# Adafruit_CAP1188.net
KiCad netlist of a schematic drawn in EAGLE
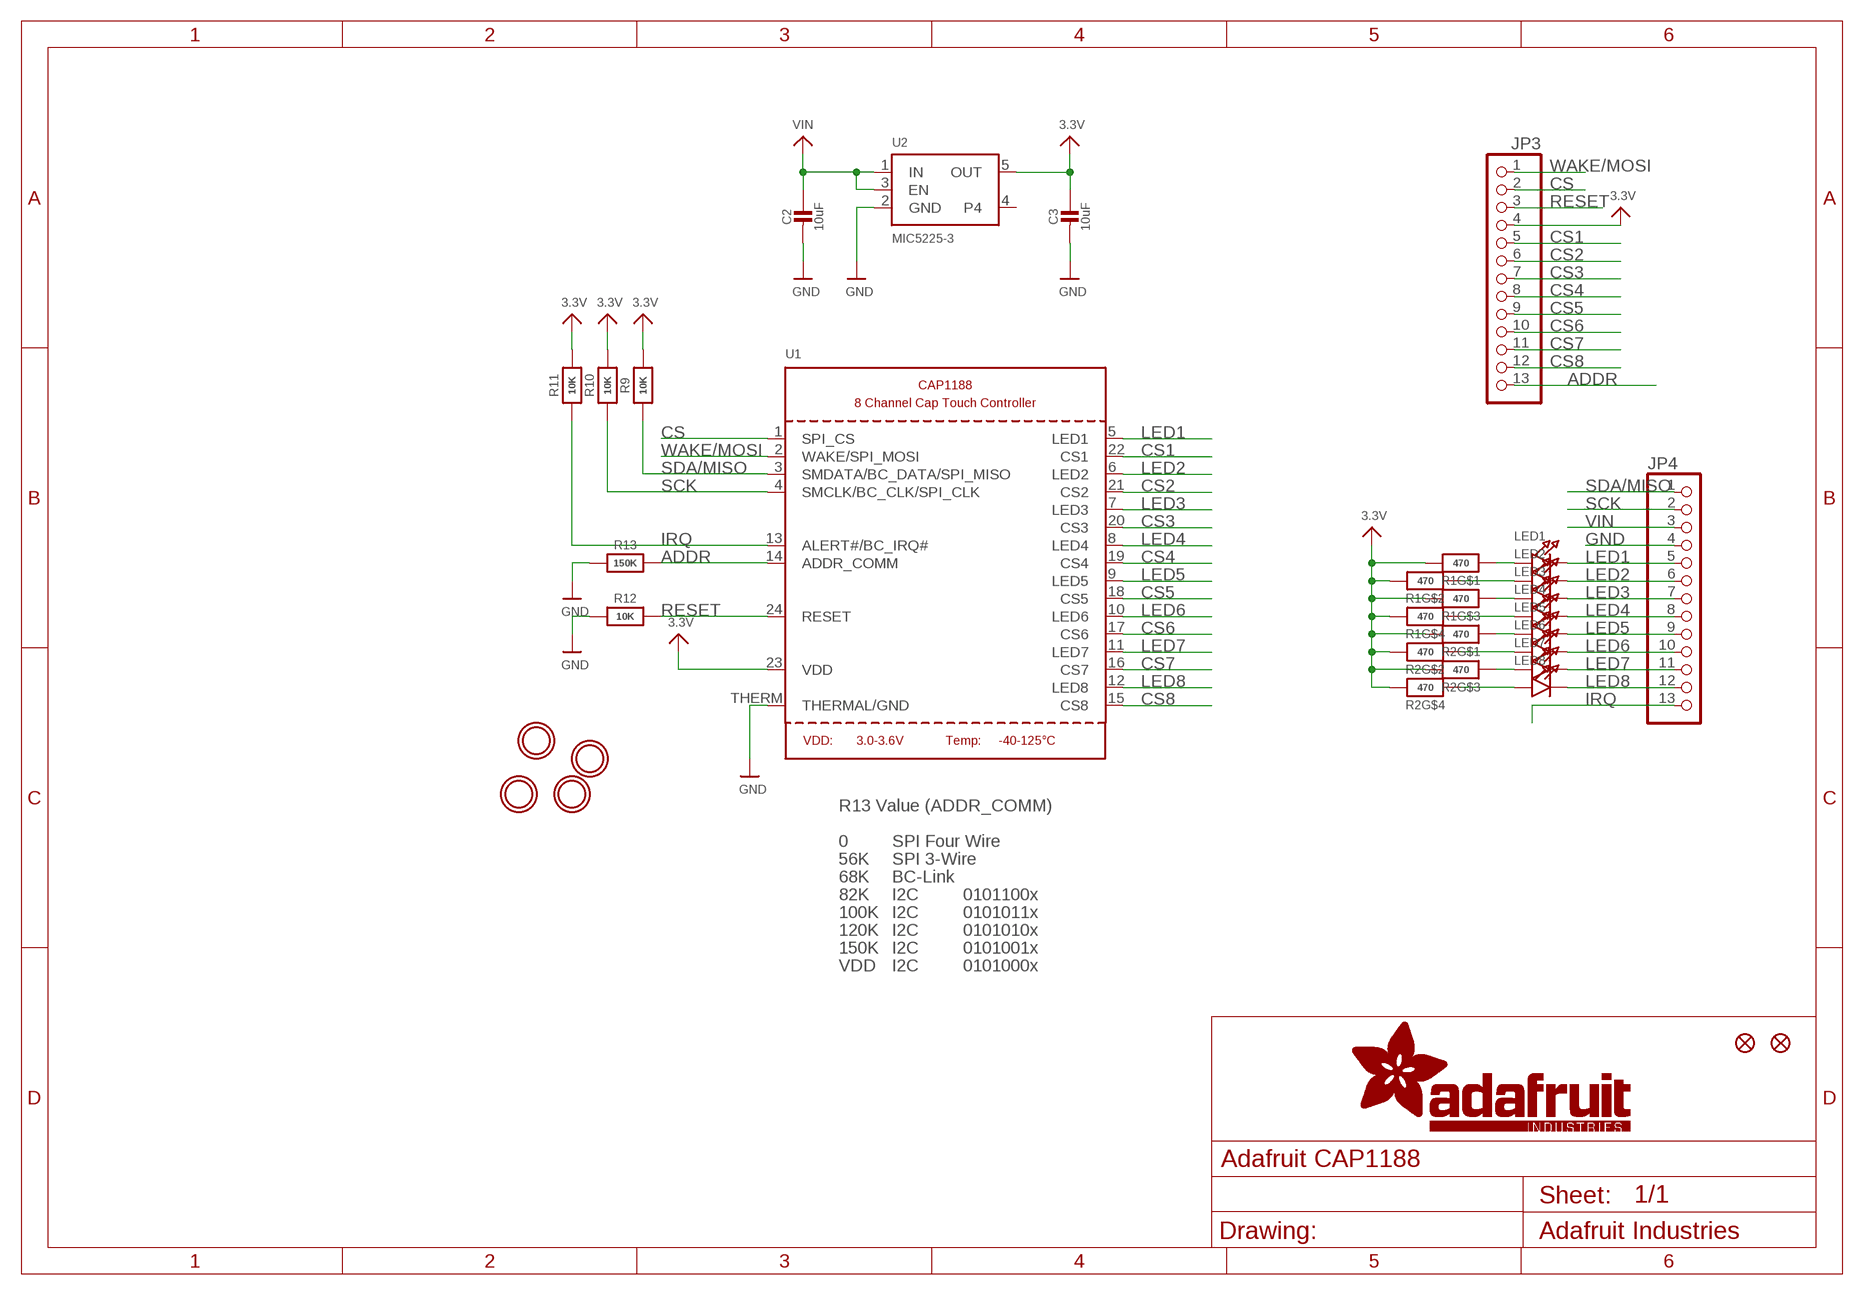
[diagram p0: schematic, sheet 1]

(export (version "E")
  (design (tool "Eeschema 10.0.6"))
  (components
    (comp (ref "C2")
      (value "10uF")
      (footprint "eagle-import:0805-NO")
      (libsource (lib "eagle-import") (part "CAP_CERAMIC0805-NOOUTLINE"))
    )
    (comp (ref "C3")
      (value "10uF")
      (footprint "eagle-import:0805-NO")
      (libsource (lib "eagle-import") (part "CAP_CERAMIC0805-NOOUTLINE"))
    )
    (comp (ref "FID1")
      (value "FIDUCIAL\"\"")
      (footprint "eagle-import:FIDUCIAL_1MM")
      (libsource (lib "eagle-import") (part "FIDUCIAL{dblquote}{dblquote}"))
    )
    (comp (ref "FID2")
      (value "FIDUCIAL\"\"")
      (footprint "eagle-import:FIDUCIAL_1MM")
      (libsource (lib "eagle-import") (part "FIDUCIAL{dblquote}{dblquote}"))
    )
    (comp (ref "JP3")
      (value "HEADER-1X13")
      (footprint "eagle-import:1X13_ROUND_70")
      (libsource (lib "eagle-import") (part "HEADER-1X13"))
    )
    (comp (ref "JP4")
      (value "HEADER-1X13")
      (footprint "eagle-import:1X13_ROUND_70")
      (libsource (lib "eagle-import") (part "HEADER-1X13"))
    )
    (comp (ref "LED1")
      (value "LED0805")
      (footprint "eagle-import:CHIPLED_0805")
      (libsource (lib "eagle-import") (part "LED0805"))
    )
    (comp (ref "LED2")
      (value "LED0805")
      (footprint "eagle-import:CHIPLED_0805")
      (libsource (lib "eagle-import") (part "LED0805"))
    )
    (comp (ref "LED3")
      (value "LED0805")
      (footprint "eagle-import:CHIPLED_0805")
      (libsource (lib "eagle-import") (part "LED0805"))
    )
    (comp (ref "LED4")
      (value "LED0805")
      (footprint "eagle-import:CHIPLED_0805")
      (libsource (lib "eagle-import") (part "LED0805"))
    )
    (comp (ref "LED5")
      (value "LED0805")
      (footprint "eagle-import:CHIPLED_0805")
      (libsource (lib "eagle-import") (part "LED0805"))
    )
    (comp (ref "LED6")
      (value "LED0805")
      (footprint "eagle-import:CHIPLED_0805")
      (libsource (lib "eagle-import") (part "LED0805"))
    )
    (comp (ref "LED7")
      (value "LED0805")
      (footprint "eagle-import:CHIPLED_0805")
      (libsource (lib "eagle-import") (part "LED0805"))
    )
    (comp (ref "LED8")
      (value "LED0805")
      (footprint "eagle-import:CHIPLED_0805")
      (libsource (lib "eagle-import") (part "LED0805"))
    )
    (comp (ref "R1")
      (value "470")
      (footprint "eagle-import:RESPACK_4X0603")
      (libsource (lib "eagle-import") (part "RESISTOR_4PACK"))
    )
    (comp (ref "R2")
      (value "470")
      (footprint "eagle-import:RESPACK_4X0603")
      (libsource (lib "eagle-import") (part "RESISTOR_4PACK"))
    )
    (comp (ref "R9")
      (value "10K")
      (footprint "eagle-import:0805-NO")
      (libsource (lib "eagle-import") (part "RESISTOR0805_NOOUTLINE"))
    )
    (comp (ref "R10")
      (value "10K")
      (footprint "eagle-import:0805-NO")
      (libsource (lib "eagle-import") (part "RESISTOR0805_NOOUTLINE"))
    )
    (comp (ref "R11")
      (value "10K")
      (footprint "eagle-import:0805-NO")
      (libsource (lib "eagle-import") (part "RESISTOR0805_NOOUTLINE"))
    )
    (comp (ref "R12")
      (value "10K")
      (footprint "eagle-import:0805-NO")
      (libsource (lib "eagle-import") (part "RESISTOR0805_NOOUTLINE"))
    )
    (comp (ref "R13")
      (value "150K")
      (footprint "eagle-import:_0805MP")
      (libsource (lib "eagle-import") (part "RESISTOR_0805MP"))
    )
    (comp (ref "U$7")
      (value "MOUNTINGHOLE2.0")
      (footprint "eagle-import:MOUNTINGHOLE_2.0_PLATED")
      (libsource (lib "eagle-import") (part "MOUNTINGHOLE2.0"))
    )
    (comp (ref "U$8")
      (value "MOUNTINGHOLE2.0")
      (footprint "eagle-import:MOUNTINGHOLE_2.0_PLATED")
      (libsource (lib "eagle-import") (part "MOUNTINGHOLE2.0"))
    )
    (comp (ref "U$9")
      (value "MOUNTINGHOLE2.0")
      (footprint "eagle-import:MOUNTINGHOLE_2.0_PLATED")
      (libsource (lib "eagle-import") (part "MOUNTINGHOLE2.0"))
    )
    (comp (ref "U$10")
      (value "MOUNTINGHOLE2.0")
      (footprint "eagle-import:MOUNTINGHOLE_2.0_PLATED")
      (libsource (lib "eagle-import") (part "MOUNTINGHOLE2.0"))
    )
    (comp (ref "U1")
      (value "CAP1188")
      (footprint "eagle-import:QFN24_4MM_SMSC")
      (libsource (lib "eagle-import") (part "CAP1188"))
    )
    (comp (ref "U2")
      (value "MIC5225-3")
      (footprint "eagle-import:SOT23-5")
      (libsource (lib "eagle-import") (part "VREG_SOT23-5"))
    )
  )
  (nets
    (net (code "1") (name "/ADDR") (class "Default")
      (node (ref "JP3") (pin "13") (pinfunction "13_13") (pintype "passive"))
      (node (ref "R13") (pin "2") (pinfunction "2_2") (pintype "passive"))
      (node (ref "U1") (pin "14") (pinfunction "ADDR_COMM_14") (pintype "bidirectional"))
    )
    (net (code "2") (name "/CS") (class "Default")
      (node (ref "JP3") (pin "2") (pinfunction "2_2") (pintype "passive"))
      (node (ref "U1") (pin "1") (pinfunction "SPI_CS_1") (pintype "input"))
    )
    (net (code "3") (name "/CS1") (class "Default")
      (node (ref "JP3") (pin "5") (pinfunction "5_5") (pintype "passive"))
      (node (ref "U1") (pin "22") (pinfunction "CS1_22") (pintype "bidirectional"))
    )
    (net (code "4") (name "/CS2") (class "Default")
      (node (ref "JP3") (pin "6") (pinfunction "6_6") (pintype "passive"))
      (node (ref "U1") (pin "21") (pinfunction "CS2_21") (pintype "bidirectional"))
    )
    (net (code "5") (name "/CS3") (class "Default")
      (node (ref "JP3") (pin "7") (pinfunction "7_7") (pintype "passive"))
      (node (ref "U1") (pin "20") (pinfunction "CS3_20") (pintype "bidirectional"))
    )
    (net (code "6") (name "/CS4") (class "Default")
      (node (ref "JP3") (pin "8") (pinfunction "8_8") (pintype "passive"))
      (node (ref "U1") (pin "19") (pinfunction "CS4_19") (pintype "bidirectional"))
    )
    (net (code "7") (name "/CS5") (class "Default")
      (node (ref "JP3") (pin "9") (pinfunction "9_9") (pintype "passive"))
      (node (ref "U1") (pin "18") (pinfunction "CS5_18") (pintype "bidirectional"))
    )
    (net (code "8") (name "/CS6") (class "Default")
      (node (ref "JP3") (pin "10") (pinfunction "10_10") (pintype "passive"))
      (node (ref "U1") (pin "17") (pinfunction "CS6_17") (pintype "bidirectional"))
    )
    (net (code "9") (name "/CS7") (class "Default")
      (node (ref "JP3") (pin "11") (pinfunction "11_11") (pintype "passive"))
      (node (ref "U1") (pin "16") (pinfunction "CS7_16") (pintype "bidirectional"))
    )
    (net (code "10") (name "/CS8") (class "Default")
      (node (ref "JP3") (pin "12") (pinfunction "12_12") (pintype "passive"))
      (node (ref "U1") (pin "15") (pinfunction "CS8_15") (pintype "bidirectional"))
    )
    (net (code "11") (name "/IRQ") (class "Default")
      (node (ref "JP4") (pin "13") (pinfunction "13_13") (pintype "passive"))
      (node (ref "R11") (pin "1") (pinfunction "1_1") (pintype "passive"))
      (node (ref "U1") (pin "13") (pinfunction "ALERT#/BC_IRQ#_13") (pintype "bidirectional"))
    )
    (net (code "12") (name "/LED1") (class "Default")
      (node (ref "JP4") (pin "5") (pinfunction "5_5") (pintype "passive"))
      (node (ref "LED1") (pin "C") (pinfunction "C_C") (pintype "passive"))
      (node (ref "U1") (pin "5") (pinfunction "LED1_5") (pintype "bidirectional"))
    )
    (net (code "13") (name "/LED2") (class "Default")
      (node (ref "JP4") (pin "6") (pinfunction "6_6") (pintype "passive"))
      (node (ref "LED2") (pin "C") (pinfunction "C_C") (pintype "passive"))
      (node (ref "U1") (pin "6") (pinfunction "LED2_6") (pintype "bidirectional"))
    )
    (net (code "14") (name "/LED3") (class "Default")
      (node (ref "JP4") (pin "7") (pinfunction "7_7") (pintype "passive"))
      (node (ref "LED3") (pin "C") (pinfunction "C_C") (pintype "passive"))
      (node (ref "U1") (pin "7") (pinfunction "LED3_7") (pintype "bidirectional"))
    )
    (net (code "15") (name "/LED4") (class "Default")
      (node (ref "JP4") (pin "8") (pinfunction "8_8") (pintype "passive"))
      (node (ref "LED4") (pin "C") (pinfunction "C_C") (pintype "passive"))
      (node (ref "U1") (pin "8") (pinfunction "LED4_8") (pintype "bidirectional"))
    )
    (net (code "16") (name "/LED5") (class "Default")
      (node (ref "JP4") (pin "9") (pinfunction "9_9") (pintype "passive"))
      (node (ref "LED5") (pin "C") (pinfunction "C_C") (pintype "passive"))
      (node (ref "U1") (pin "9") (pinfunction "LED5_9") (pintype "bidirectional"))
    )
    (net (code "17") (name "/LED6") (class "Default")
      (node (ref "JP4") (pin "10") (pinfunction "10_10") (pintype "passive"))
      (node (ref "LED6") (pin "C") (pinfunction "C_C") (pintype "passive"))
      (node (ref "U1") (pin "10") (pinfunction "LED6_10") (pintype "bidirectional"))
    )
    (net (code "18") (name "/LED7") (class "Default")
      (node (ref "JP4") (pin "11") (pinfunction "11_11") (pintype "passive"))
      (node (ref "LED7") (pin "C") (pinfunction "C_C") (pintype "passive"))
      (node (ref "U1") (pin "11") (pinfunction "LED7_11") (pintype "bidirectional"))
    )
    (net (code "19") (name "/LED8") (class "Default")
      (node (ref "JP4") (pin "12") (pinfunction "12_12") (pintype "passive"))
      (node (ref "LED8") (pin "C") (pinfunction "C_C") (pintype "passive"))
      (node (ref "U1") (pin "12") (pinfunction "LED8_12") (pintype "bidirectional"))
    )
    (net (code "20") (name "/RESET") (class "Default")
      (node (ref "JP3") (pin "3") (pinfunction "3_3") (pintype "passive"))
      (node (ref "R12") (pin "2") (pinfunction "2_2") (pintype "passive"))
      (node (ref "U1") (pin "24") (pinfunction "RESET_24") (pintype "input"))
    )
    (net (code "21") (name "/SCK") (class "Default")
      (node (ref "JP4") (pin "2") (pinfunction "2_2") (pintype "passive"))
      (node (ref "R10") (pin "1") (pinfunction "1_1") (pintype "passive"))
      (node (ref "U1") (pin "4") (pinfunction "SMCLK/BC_CLK/SPI_CLK_4") (pintype "bidirectional"))
    )
    (net (code "22") (name "/SDA{slash}MISO") (class "Default")
      (node (ref "JP4") (pin "1") (pinfunction "1_1") (pintype "passive"))
      (node (ref "R9") (pin "1") (pinfunction "1_1") (pintype "passive"))
      (node (ref "U1") (pin "3") (pinfunction "SMDATA/BC_DATA/SPI_MISO_3") (pintype "bidirectional"))
    )
    (net (code "23") (name "/WAKE{slash}MOSI") (class "Default")
      (node (ref "JP3") (pin "1") (pinfunction "1_1") (pintype "passive"))
      (node (ref "U1") (pin "2") (pinfunction "WAKE/SPI_MOSI_2") (pintype "bidirectional"))
    )
    (net (code "24") (name "3.3V") (class "Default")
      (node (ref "C3") (pin "1") (pinfunction "1_1") (pintype "passive"))
      (node (ref "JP3") (pin "4") (pinfunction "4_4") (pintype "passive"))
      (node (ref "R1") (pin "5") (pinfunction "2_5") (pintype "passive"))
      (node (ref "R1") (pin "6") (pinfunction "2_6") (pintype "passive"))
      (node (ref "R1") (pin "7") (pinfunction "2_7") (pintype "passive"))
      (node (ref "R1") (pin "8") (pinfunction "2_8") (pintype "passive"))
      (node (ref "R10") (pin "2") (pinfunction "2_2") (pintype "passive"))
      (node (ref "R11") (pin "2") (pinfunction "2_2") (pintype "passive"))
      (node (ref "R2") (pin "5") (pinfunction "2_5") (pintype "passive"))
      (node (ref "R2") (pin "6") (pinfunction "2_6") (pintype "passive"))
      (node (ref "R2") (pin "7") (pinfunction "2_7") (pintype "passive"))
      (node (ref "R2") (pin "8") (pinfunction "2_8") (pintype "passive"))
      (node (ref "R9") (pin "2") (pinfunction "2_2") (pintype "passive"))
      (node (ref "U1") (pin "23") (pinfunction "VDD_23") (pintype "power_in"))
      (node (ref "U2") (pin "5") (pinfunction "OUT_5") (pintype "power_in"))
    )
    (net (code "25") (name "GND") (class "Default")
      (node (ref "C2") (pin "2") (pinfunction "2_2") (pintype "passive"))
      (node (ref "C3") (pin "2") (pinfunction "2_2") (pintype "passive"))
      (node (ref "JP4") (pin "4") (pinfunction "4_4") (pintype "passive"))
      (node (ref "R12") (pin "1") (pinfunction "1_1") (pintype "passive"))
      (node (ref "R13") (pin "1") (pinfunction "1_1") (pintype "passive"))
      (node (ref "U1") (pin "THERM") (pinfunction "THERMAL/GND_THERM") (pintype "power_in"))
      (node (ref "U2") (pin "2") (pinfunction "GND_2") (pintype "power_in"))
    )
    (net (code "26") (name "Net-(LED1-PadA)") (class "Default")
      (node (ref "LED1") (pin "A") (pinfunction "A_A") (pintype "passive"))
      (node (ref "R1") (pin "1") (pinfunction "1_1") (pintype "passive"))
    )
    (net (code "27") (name "Net-(LED5-PadA)") (class "Default")
      (node (ref "LED5") (pin "A") (pinfunction "A_A") (pintype "passive"))
      (node (ref "R2") (pin "1") (pinfunction "1_1") (pintype "passive"))
    )
    (net (code "28") (name "Net-(R1B-1)") (class "Default")
      (node (ref "LED2") (pin "A") (pinfunction "A_A") (pintype "passive"))
      (node (ref "R1") (pin "2") (pinfunction "1_2") (pintype "passive"))
    )
    (net (code "29") (name "Net-(R1C-1)") (class "Default")
      (node (ref "LED3") (pin "A") (pinfunction "A_A") (pintype "passive"))
      (node (ref "R1") (pin "3") (pinfunction "1_3") (pintype "passive"))
    )
    (net (code "30") (name "Net-(R1D-1)") (class "Default")
      (node (ref "LED4") (pin "A") (pinfunction "A_A") (pintype "passive"))
      (node (ref "R1") (pin "4") (pinfunction "1_4") (pintype "passive"))
    )
    (net (code "31") (name "Net-(R2B-1)") (class "Default")
      (node (ref "LED6") (pin "A") (pinfunction "A_A") (pintype "passive"))
      (node (ref "R2") (pin "2") (pinfunction "1_2") (pintype "passive"))
    )
    (net (code "32") (name "Net-(R2C-1)") (class "Default")
      (node (ref "LED7") (pin "A") (pinfunction "A_A") (pintype "passive"))
      (node (ref "R2") (pin "3") (pinfunction "1_3") (pintype "passive"))
    )
    (net (code "33") (name "Net-(R2D-1)") (class "Default")
      (node (ref "LED8") (pin "A") (pinfunction "A_A") (pintype "passive"))
      (node (ref "R2") (pin "4") (pinfunction "1_4") (pintype "passive"))
    )
    (net (code "34") (name "VIN") (class "Default")
      (node (ref "C2") (pin "1") (pinfunction "1_1") (pintype "passive"))
      (node (ref "JP4") (pin "3") (pinfunction "3_3") (pintype "passive"))
      (node (ref "U2") (pin "1") (pinfunction "IN_1") (pintype "power_in"))
      (node (ref "U2") (pin "3") (pinfunction "EN_3") (pintype "input"))
    )
    (net (code "35") (name "unconnected-(U2-P4-Pad4)") (class "Default")
      (node (ref "U2") (pin "4") (pinfunction "P4_4") (pintype "bidirectional"))
    )
  )
)
